# PROC051D_CAN_Interface.net
KiCad netlist of a schematic drawn in Altium Designer
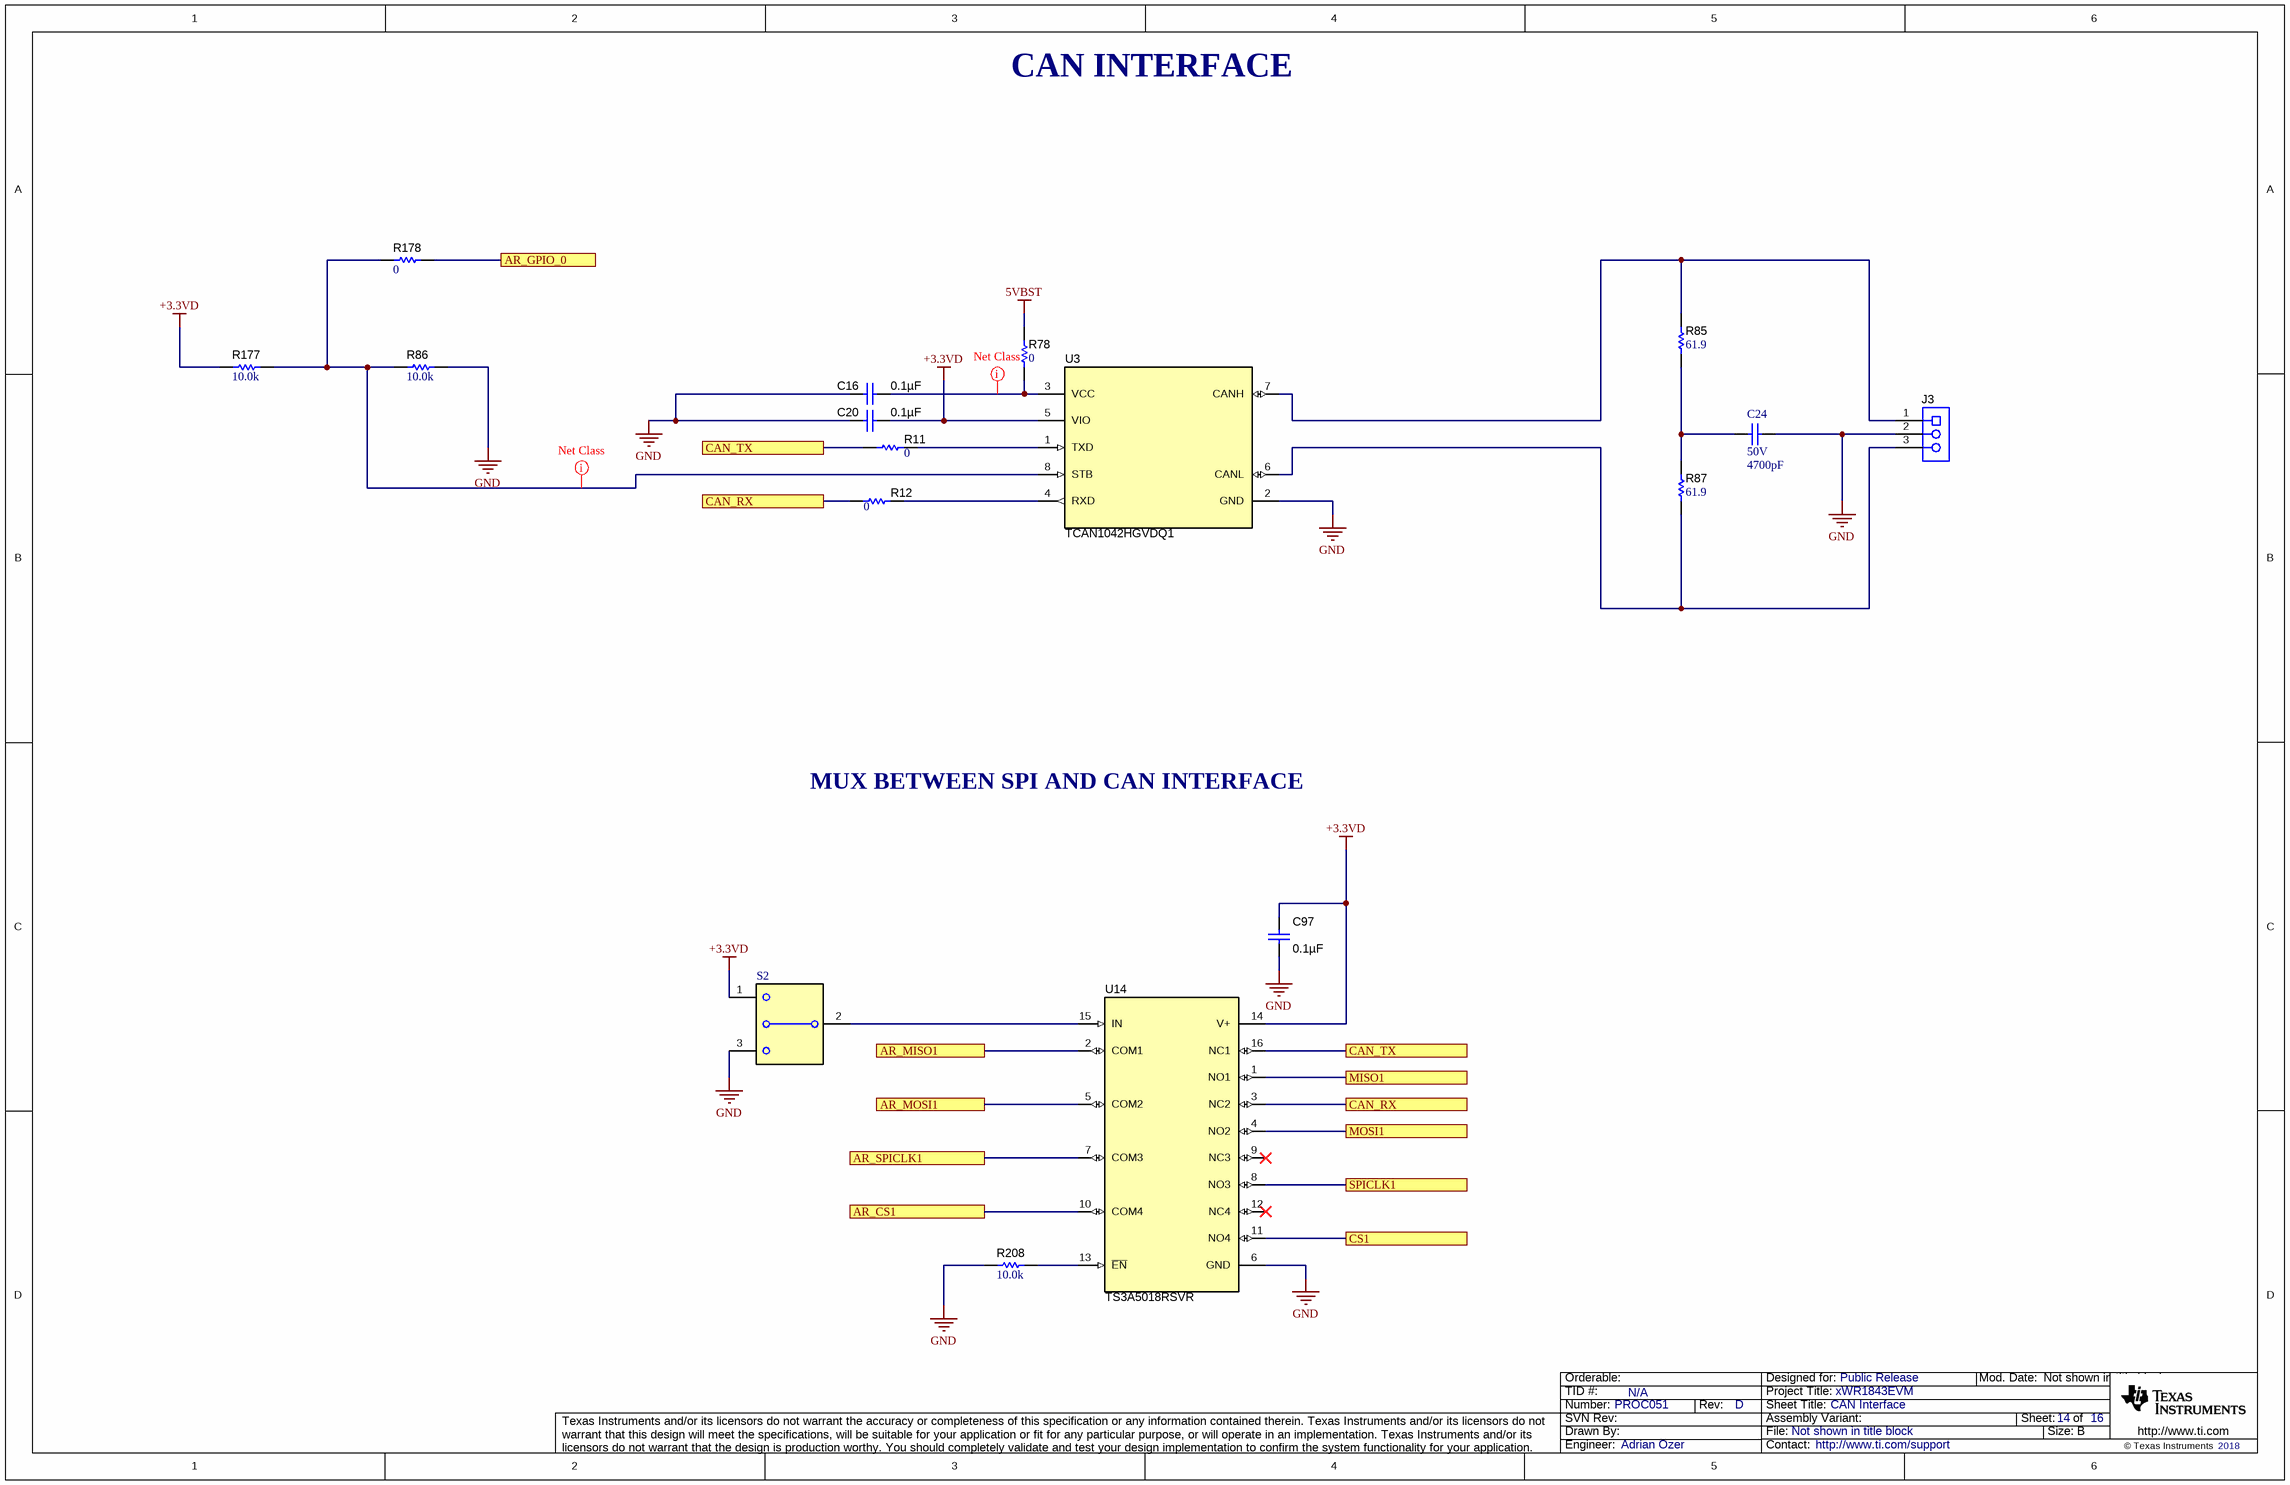
[diagram p0: PROC051D_CAN_Interface.SchDoc]

(export (version "E")
  (design (tool "Eeschema 10.0.6"))
  (components
    (comp (ref "C16")
      (value "C0402C104K8RACTU")
      (footprint "0402L")
      (description "CAP, CERM, 0.1 µF, 10 V,+/- 10%, X7R, 0402")
      (fields (field (name "MANUFACTURER") "Kemet") (field (name "VALUEDISPLAYED") "0.1µF"))
      (libsource (lib "Altium Vault - TI") (part "Capacitor"))
    )
    (comp (ref "C20")
      (value "C0402C104K8RACTU")
      (footprint "0402L")
      (description "CAP, CERM, 0.1 µF, 10 V,+/- 10%, X7R, 0402")
      (fields (field (name "MANUFACTURER") "Kemet") (field (name "VALUEDISPLAYED") "0.1µF"))
      (libsource (lib "Altium Vault - TI") (part "Capacitor"))
    )
    (comp (ref "C24")
      (value "GCM155R71H472KA37D")
      (footprint "0402")
      (description "CAP, CERM, 4700 pF, 50 V, +/- 10%, X7R, AEC-Q200 Grade 1, 0402")
      (fields
        (field (name "MANUFACTURER") "MuRata")
        (field (name "VDC_V") "50V")
        (field (name "VALUEDISPLAYED") "4700pF")
        (field (name "PUBLISHER") "Texas Instruments")
      )
      (libsource (lib "Altium Vault - TI") (part "Capacitor"))
    )
    (comp (ref "C97")
      (value "C0402C104K8RACTU")
      (footprint "0402L")
      (description "CAP, CERM, 0.1 µF, 10 V,+/- 10%, X7R, 0402")
      (fields (field (name "MANUFACTURER") "Kemet") (field (name "VALUEDISPLAYED") "0.1µF"))
      (libsource (lib "Altium Vault - TI") (part "Capacitor"))
    )
    (comp (ref "J3")
      (value "OSTTE030161")
      (footprint "On-Shore_OSTTE030161")
      (description "Terminal Block, 3.5mm, 3x1, Tin, R/A, TH")
      (fields
        (field (name "MANUFACTURER") "On-Shore Technology")
        (field (name "PUBLISHER") "Texas Instruments")
      )
      (libsource (lib "Altium Vault - TI") (part "Receptacle_3x1"))
    )
    (comp (ref "R11")
      (value "0")
      (footprint "0402L")
      (description "RES, 0, 5%, 0.1 W, AEC-Q200 Grade 0, 0402")
      (fields (field (name "MANUFACTURER") "Panasonic") (field (name "PARTNUMBER") "ERJ-2GE0R00X"))
      (libsource (lib "Altium Vault - TI") (part "Resistor"))
    )
    (comp (ref "R12")
      (value "ERJ-2GE0R00X")
      (footprint "0402L")
      (description "RES, 0, 5%, 0.1 W, AEC-Q200 Grade 0, 0402")
      (fields (field (name "MANUFACTURER") "Panasonic") (field (name "VALUEDISPLAYED") "0"))
      (libsource (lib "Altium Vault - TI") (part "Resistor"))
    )
    (comp (ref "R78")
      (value "ERJ-2GE0R00X")
      (footprint "0402L")
      (description "RES, 0, 5%, 0.1 W, AEC-Q200 Grade 0, 0402")
      (fields (field (name "MANUFACTURER") "Panasonic") (field (name "VALUEDISPLAYED") "0"))
      (libsource (lib "Altium Vault - TI") (part "Resistor"))
    )
    (comp (ref "R85")
      (value "CRCW040261R9FKED")
      (footprint "0402L")
      (description "RES, 61.9, 1%, 0.063 W, AEC-Q200 Grade 0, 0402")
      (fields (field (name "MANUFACTURER") "Vishay-Dale") (field (name "VALUEDISPLAYED") "61.9"))
      (libsource (lib "Altium Vault - TI") (part "Resistor"))
    )
    (comp (ref "R86")
      (value "CRCW040210K0FKED")
      (footprint "0402L")
      (description "RES, 10.0 k, 1%, 0.063 W, AEC-Q200 Grade 0, 0402")
      (fields (field (name "MANUFACTURER") "Vishay-Dale") (field (name "VALUEDISPLAYED") "10.0k"))
      (libsource (lib "Altium Vault - TI") (part "Resistor"))
    )
    (comp (ref "R87")
      (value "CRCW040261R9FKED")
      (footprint "0402L")
      (description "RES, 61.9, 1%, 0.063 W, AEC-Q200 Grade 0, 0402")
      (fields (field (name "MANUFACTURER") "Vishay-Dale") (field (name "VALUEDISPLAYED") "61.9"))
      (libsource (lib "Altium Vault - TI") (part "Resistor"))
    )
    (comp (ref "R177")
      (value "CRCW040210K0FKED")
      (footprint "0402L")
      (description "RES, 10.0 k, 1%, 0.063 W, AEC-Q200 Grade 0, 0402")
      (fields (field (name "MANUFACTURER") "Vishay-Dale") (field (name "VALUEDISPLAYED") "10.0k"))
      (libsource (lib "Altium Vault - TI") (part "Resistor"))
    )
    (comp (ref "R178")
      (value "ERJ-2GE0R00X")
      (footprint "0402L")
      (description "RES, 0, 5%, 0.1 W, AEC-Q200 Grade 0, 0402")
      (fields (field (name "MANUFACTURER") "Panasonic") (field (name "VALUEDISPLAYED") "0"))
      (libsource (lib "Altium Vault - TI") (part "Resistor"))
    )
    (comp (ref "R208")
      (value "CRCW040210K0FKED")
      (footprint "0402L")
      (description "RES, 10.0 k, 1%, 0.063 W, AEC-Q200 Grade 0, 0402")
      (fields (field (name "MANUFACTURER") "Vishay-Dale") (field (name "VALUEDISPLAYED") "10.0k"))
      (libsource (lib "Altium Vault - TI") (part "Resistor"))
    )
    (comp (ref "S2")
      (value "CJS-1201TA")
      (footprint "SW_CJS_1201A")
      (description "Slide SW, SPDT 0.1A 50VDC")
      (fields
        (field (name "MANUFACTURER") "Copal Electronics")
        (field (name "PUBLISHER") "Texas Instruments")
      )
      (libsource (lib "Altium Vault - TI") (part "SW_SPDT_ON-OFF-ON_COM2_1_3"))
    )
    (comp (ref "U3")
      (value "TCAN1042HGVDQ1")
      (footprint "D0008A_L")
      (description "Automotive Fault Protected CAN Transceiver With Flexible Data-Rate, D0008A (SOIC-8)")
      (fields
        (field (name "PARTNUMBER") "TCAN1042HGVDQ1")
        (field (name "MANUFACTURER") "Texas Instruments")
        (field (name "ALTERNATE PARTNUMBER") "TCAN1042HGVDRQ1")
        (field (name "PUBLISHER") "Texas Instruments")
      )
      (libsource (lib "Altium Vault - TI") (part "TCAN1042_V"))
    )
    (comp (ref "U14")
      (value "TS3A5018RSVR")
      (footprint "RSV0016A")
      (description "10-Ohm Quad SPDT Analog Switch, RSV0016A (UQFN-16)")
      (fields
        (field (name "MANUFACTURER") "Texas Instruments")
        (field (name "PARTNUMBER") "TS3A5018RSVR")
        (field (name "PUBLISHER") "Texas Instruments")
      )
      (libsource (lib "Altium Vault - TI") (part "CMP-0067415-1"))
    )
  )
  (nets
    (net (code "1") (name "+3.3VD") (class "Default")
      (node (ref "C20") (pin "2") (pinfunction "2_2") (pintype "passive"))
      (node (ref "C97") (pin "2") (pinfunction "2_2") (pintype "passive"))
      (node (ref "R177") (pin "1") (pinfunction "1_1") (pintype "passive"))
      (node (ref "S2") (pin "1") (pinfunction "1_1") (pintype "passive"))
      (node (ref "U14") (pin "14") (pinfunction "V+_14") (pintype "power_in"))
      (node (ref "U3") (pin "5") (pinfunction "VIO_5") (pintype "power_in"))
    )
    (net (code "2") (name "/AR_CS1") (class "Default")
      (node (ref "U14") (pin "10") (pinfunction "COM4_10") (pintype "bidirectional"))
    )
    (net (code "3") (name "/AR_GPIO_0") (class "Default")
      (node (ref "R178") (pin "2") (pinfunction "2_2") (pintype "passive"))
    )
    (net (code "4") (name "/AR_MISO1") (class "Default")
      (node (ref "U14") (pin "2") (pinfunction "COM1_2") (pintype "bidirectional"))
    )
    (net (code "5") (name "/AR_MOSI1") (class "Default")
      (node (ref "U14") (pin "5") (pinfunction "COM2_5") (pintype "bidirectional"))
    )
    (net (code "6") (name "/AR_SPICLK1") (class "Default")
      (node (ref "U14") (pin "7") (pinfunction "COM3_7") (pintype "bidirectional"))
    )
    (net (code "7") (name "/CAN_RX") (class "Default")
      (node (ref "R12") (pin "1") (pinfunction "1_1") (pintype "passive"))
      (node (ref "U14") (pin "3") (pinfunction "NC2_3") (pintype "bidirectional"))
    )
    (net (code "8") (name "/CAN_TX") (class "Default")
      (node (ref "R11") (pin "1") (pinfunction "1_1") (pintype "passive"))
      (node (ref "U14") (pin "16") (pinfunction "NC1_16") (pintype "bidirectional"))
    )
    (net (code "9") (name "/CS1") (class "Default")
      (node (ref "U14") (pin "11") (pinfunction "NO4_11") (pintype "bidirectional"))
    )
    (net (code "10") (name "/MISO1") (class "Default")
      (node (ref "U14") (pin "1") (pinfunction "NO1_1") (pintype "bidirectional"))
    )
    (net (code "11") (name "/MOSI1") (class "Default")
      (node (ref "U14") (pin "4") (pinfunction "NO2_4") (pintype "bidirectional"))
    )
    (net (code "12") (name "/SPICLK1") (class "Default")
      (node (ref "U14") (pin "8") (pinfunction "NO3_8") (pintype "bidirectional"))
    )
    (net (code "13") (name "5VBST") (class "Default")
      (node (ref "R78") (pin "2") (pinfunction "2_2") (pintype "passive"))
    )
    (net (code "14") (name "GND") (class "Default")
      (node (ref "C16") (pin "1") (pinfunction "1_1") (pintype "passive"))
      (node (ref "C20") (pin "1") (pinfunction "1_1") (pintype "passive"))
      (node (ref "C24") (pin "1") (pinfunction "1_1") (pintype "passive"))
      (node (ref "C97") (pin "1") (pinfunction "1_1") (pintype "passive"))
      (node (ref "J3") (pin "2") (pinfunction "2_2") (pintype "passive"))
      (node (ref "R208") (pin "2") (pinfunction "2_2") (pintype "passive"))
      (node (ref "R86") (pin "2") (pinfunction "2_2") (pintype "passive"))
      (node (ref "S2") (pin "3") (pinfunction "3_3") (pintype "passive"))
      (node (ref "U14") (pin "6") (pinfunction "GND_6") (pintype "power_in"))
      (node (ref "U3") (pin "2") (pinfunction "GND_2") (pintype "power_in"))
    )
    (net (code "15") (name "Net-(C24-Pad2)") (class "Default")
      (node (ref "C24") (pin "2") (pinfunction "2_2") (pintype "passive"))
      (node (ref "R85") (pin "1") (pinfunction "1_1") (pintype "passive"))
      (node (ref "R87") (pin "2") (pinfunction "2_2") (pintype "passive"))
    )
    (net (code "16") (name "Net-(S2-COM)") (class "Default")
      (node (ref "S2") (pin "2") (pinfunction "COM_2") (pintype "passive"))
      (node (ref "U14") (pin "15") (pinfunction "IN_15") (pintype "input"))
    )
    (net (code "17") (name "Net-(U3-CANH)") (class "Default")
      (node (ref "J3") (pin "1") (pinfunction "1_1") (pintype "passive"))
      (node (ref "R85") (pin "2") (pinfunction "2_2") (pintype "passive"))
      (node (ref "U3") (pin "7") (pinfunction "CANH_7") (pintype "bidirectional"))
    )
    (net (code "18") (name "Net-(U3-CANL)") (class "Default")
      (node (ref "J3") (pin "3") (pinfunction "3_3") (pintype "passive"))
      (node (ref "R87") (pin "1") (pinfunction "1_1") (pintype "passive"))
      (node (ref "U3") (pin "6") (pinfunction "CANL_6") (pintype "bidirectional"))
    )
    (net (code "19") (name "Net-(U3-RXD)") (class "Default")
      (node (ref "R12") (pin "2") (pinfunction "2_2") (pintype "passive"))
      (node (ref "U3") (pin "4") (pinfunction "RXD_4") (pintype "output"))
    )
    (net (code "20") (name "Net-(U3-STB)") (class "Default")
      (node (ref "R177") (pin "2") (pinfunction "2_2") (pintype "passive"))
      (node (ref "R178") (pin "1") (pinfunction "1_1") (pintype "passive"))
      (node (ref "R86") (pin "1") (pinfunction "1_1") (pintype "passive"))
      (node (ref "U3") (pin "8") (pinfunction "STB_8") (pintype "input"))
    )
    (net (code "21") (name "Net-(U3-TXD)") (class "Default")
      (node (ref "R11") (pin "2") (pinfunction "2_2") (pintype "passive"))
      (node (ref "U3") (pin "1") (pinfunction "TXD_1") (pintype "input"))
    )
    (net (code "22") (name "Net-(U3-VCC)") (class "Default")
      (node (ref "C16") (pin "2") (pinfunction "2_2") (pintype "passive"))
      (node (ref "R78") (pin "1") (pinfunction "1_1") (pintype "passive"))
      (node (ref "U3") (pin "3") (pinfunction "VCC_3") (pintype "power_in"))
    )
    (net (code "23") (name "Net-(U14-EN)") (class "Default")
      (node (ref "R208") (pin "1") (pinfunction "1_1") (pintype "passive"))
      (node (ref "U14") (pin "13") (pinfunction "EN_13") (pintype "input"))
    )
    (net (code "24") (name "unconnected-(U14-NC3-Pad9)") (class "Default")
      (node (ref "U14") (pin "9") (pinfunction "NC3_9") (pintype "bidirectional+no_connect"))
    )
    (net (code "25") (name "unconnected-(U14-NC4-Pad12)") (class "Default")
      (node (ref "U14") (pin "12") (pinfunction "NC4_12") (pintype "bidirectional+no_connect"))
    )
  )
)
